# list1.net
KiCad netlist of a schematic drawn in Altium Designer
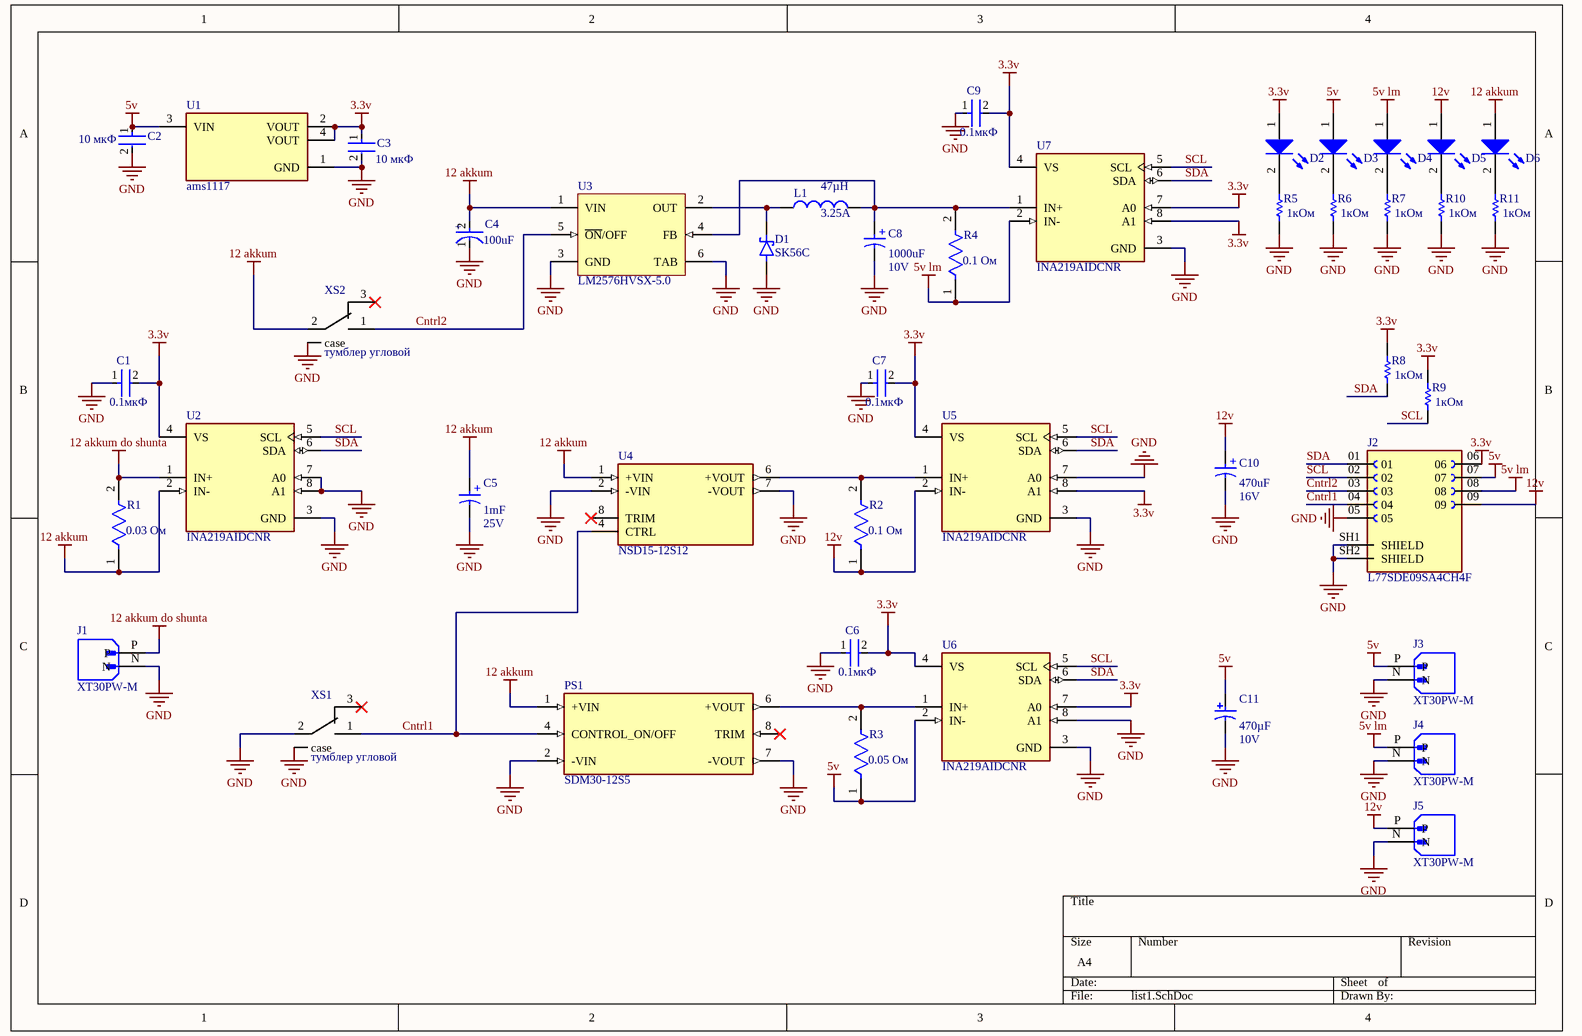
[diagram p0: list1.SchDoc]

(export (version "E")
  (design (tool "Eeschema 10.0.6"))
  (components
    (comp (ref "C1")
      (value "0.1мкФ")
      (footprint "FP-C0805C-DN-IPC_A")
      (description "CAP CER 0.1UF 50V X7R 0805")
      (fields
        (field (name "MANUFACTURER PART NUMBER") "C0805C104K5RACTU")
        (field (name "MANUFACTURER") "KEMET")
      )
      (libsource (lib "Components - cap0805") (part "CMP-2007-00279-2"))
    )
    (comp (ref "C2")
      (value "10 мкФ")
      (footprint "FP-C0805C-DN-IPC_A")
      (description "CAP CER 10UF 50V X7R 0805")
      (fields
        (field (name "MANUFACTURER PART NUMBER") "C0805C104K5RACTU")
        (field (name "MANUFACTURER") "KEMET")
      )
      (libsource (lib "Components - cap0805") (part "CMP-2007-00279-2"))
    )
    (comp (ref "C3")
      (value "10 мкФ")
      (footprint "FP-C0805C-DN-IPC_A")
      (description "CAP CER 10UF 50V X7R 0805")
      (fields
        (field (name "MANUFACTURER PART NUMBER") "C0805C104K5RACTU")
        (field (name "MANUFACTURER") "KEMET")
      )
      (libsource (lib "Components - cap0805") (part "CMP-2007-00279-2"))
    )
    (comp (ref "C4")
      (value "T495D107K016ATE125")
      (footprint "FP-T495D107K016ATE125-MFG")
      (description "CAP TANT 100UF 10% 16V 2917")
      (fields
        (field (name "CAPACITANCE") "100uF")
        (field (name "VOLTAGE") "16V")
        (field (name "TOLERANCE") "10%")
      )
      (libsource (lib "Altium Content Vault") (part "a00bbbee19879c290e62620ae7e47b1"))
    )
    (comp (ref "C5")
      (value "865060257010")
      (footprint "10*12.5")
      (description "865060257010 WCAP-ASLL Aluminum Electrolytic Capacitors 1000uf 25V")
      (fields
        (field (name "VOLTAGE RATING") "25V")
        (field (name "CAPACITANCE") "1mF")
        (field (name "TOLERANCE") "20%")
      )
      (libsource (lib "Components - 06.07.24 - 21") (part "konder"))
    )
    (comp (ref "C6")
      (value "0.1мкФ")
      (footprint "FP-C0805C-DN-IPC_A")
      (description "CAP CER 0.1UF 50V X7R 0805")
      (fields
        (field (name "MANUFACTURER PART NUMBER") "C0805C104K5RACTU")
        (field (name "MANUFACTURER") "KEMET")
      )
      (libsource (lib "Components - cap0805") (part "CMP-2007-00279-2"))
    )
    (comp (ref "C7")
      (value "0.1мкФ")
      (footprint "FP-C0805C-DN-IPC_A")
      (description "CAP CER 0.1UF 50V X7R 0805")
      (fields
        (field (name "MANUFACTURER PART NUMBER") "C0805C104K5RACTU")
        (field (name "MANUFACTURER") "KEMET")
      )
      (libsource (lib "Components - cap0805") (part "CMP-2007-00279-2"))
    )
    (comp (ref "C8")
      (value "865060257010")
      (footprint "WCAP-ASLL_D10H10.5")
      (description "865060257010 WCAP-ASLL Aluminum Electrolytic Capacitors 1000uf 10v")
      (fields
        (field (name "VOLTAGE RATING") "10V")
        (field (name "CAPACITANCE") "1000uF")
        (field (name "TOLERANCE") "20%")
      )
      (libsource (lib "Components - 06.07.24 - 21") (part "CMP-03913-54202466-2"))
    )
    (comp (ref "C9")
      (value "0.1мкФ")
      (footprint "FP-C0805C-DN-IPC_A")
      (description "CAP CER 0.1UF 50V X7R 0805")
      (fields
        (field (name "MANUFACTURER PART NUMBER") "C0805C104K5RACTU")
        (field (name "MANUFACTURER") "KEMET")
      )
      (libsource (lib "Components - cap0805") (part "CMP-2007-00279-2"))
    )
    (comp (ref "C10")
      (value "865060257010")
      (footprint "WCAP-ASLL_D10H10.5")
      (description "865060257010 WCAP-ASLL Aluminum Electrolytic Capacitors 470uf 16v")
      (fields
        (field (name "VOLTAGE RATING") "16V")
        (field (name "CAPACITANCE") "470uF")
        (field (name "TOLERANCE") "20%")
      )
      (libsource (lib "Components - 06.07.24 - 21") (part "CMP-03913-54202466-2"))
    )
    (comp (ref "C11")
      (value "EEEFK1C471P")
      (footprint "PNSC-FK-V-F_V")
      (fields
        (field (name "CAPACITANCE") "470µF")
        (field (name "MANUFACTURER") "Panasonic")
        (field (name "RATED VOLTAGE") "10V")
      )
      (libsource (lib "Altium Content Vault") (part "CAP-P-2"))
    )
    (comp (ref "D1")
      (value "SK56C")
      (footprint "DIOM6859X262N")
      (description "5A, 60V, Schottky Rectifier")
      (fields (field (name "MF") "Taiwan Semiconductor"))
      (libsource (lib "SK56C") (part "SK56C"))
    )
    (comp (ref "D2")
      (value "Infrared, 1.5V, 30°")
      (footprint "WL-TIRC_3mm")
      (description "WL-TIRC THT Infrared Round Waterclear, 3mm, 60mW/sr, Infrared, 1.5V, 30°")
      (fields
        (field (name "MANUFACTURER PART NUMBER") "15400385F3590")
        (field (name "MANUFACTURER") "Wurth Elektronik")
      )
      (libsource (lib "WL-TIRC") (part "15400385F3590"))
    )
    (comp (ref "D3")
      (value "Infrared, 1.5V, 30°")
      (footprint "WL-TIRC_3mm")
      (description "WL-TIRC THT Infrared Round Waterclear, 3mm, 60mW/sr, Infrared, 1.5V, 30°")
      (fields
        (field (name "MANUFACTURER PART NUMBER") "15400385F3590")
        (field (name "MANUFACTURER") "Wurth Elektronik")
      )
      (libsource (lib "WL-TIRC") (part "15400385F3590"))
    )
    (comp (ref "D4")
      (value "Infrared, 1.5V, 30°")
      (footprint "WL-TIRC_3mm")
      (description "WL-TIRC THT Infrared Round Waterclear, 3mm, 60mW/sr, Infrared, 1.5V, 30°")
      (fields
        (field (name "MANUFACTURER PART NUMBER") "15400385F3590")
        (field (name "MANUFACTURER") "Wurth Elektronik")
      )
      (libsource (lib "WL-TIRC") (part "15400385F3590"))
    )
    (comp (ref "D5")
      (value "Infrared, 1.5V, 30°")
      (footprint "WL-TIRC_3mm")
      (description "WL-TIRC THT Infrared Round Waterclear, 3mm, 60mW/sr, Infrared, 1.5V, 30°")
      (fields
        (field (name "MANUFACTURER PART NUMBER") "15400385F3590")
        (field (name "MANUFACTURER") "Wurth Elektronik")
      )
      (libsource (lib "WL-TIRC") (part "15400385F3590"))
    )
    (comp (ref "D6")
      (value "Infrared, 1.5V, 30°")
      (footprint "WL-TIRC_3mm")
      (description "WL-TIRC THT Infrared Round Waterclear, 3mm, 60mW/sr, Infrared, 1.5V, 30°")
      (fields
        (field (name "MANUFACTURER PART NUMBER") "15400385F3590")
        (field (name "MANUFACTURER") "Wurth Elektronik")
      )
      (libsource (lib "WL-TIRC") (part "15400385F3590"))
    )
    (comp (ref "J1")
      (value "XT30PW-M")
      (footprint "AMASS_XT30PW-M")
      (description "Socket; DC supply; XT30; male; PIN: 2; on PCBs; THT; Colour: yellow")
      (fields (field (name "MF") "AMASS"))
      (libsource (lib "XT30PW-M") (part "XT30PW-M"))
    )
    (comp (ref "J2")
      (value "L77SDE09SA4CH4F")
      (footprint "AMPHENOL_L77SDE09SA4CH4F")
      (fields (field (name "MF") "Amphenol ICC (Commercial Products)"))
      (libsource (lib "L77SDE09SA4CH4F") (part "L77SDE09SA4CH4F"))
    )
    (comp (ref "J3")
      (value "XT30PW-M")
      (footprint "AMASS_XT30PW-M")
      (description "Socket; DC supply; XT30; male; PIN: 2; on PCBs; THT; Colour: yellow")
      (fields (field (name "MF") "AMASS"))
      (libsource (lib "") (part "XT30PW-M_1"))
    )
    (comp (ref "J4")
      (value "XT30PW-M")
      (footprint "AMASS_XT30PW-M")
      (description "Socket; DC supply; XT30; male; PIN: 2; on PCBs; THT; Colour: yellow")
      (fields (field (name "MF") "AMASS"))
      (libsource (lib "") (part "XT30PW-M_1"))
    )
    (comp (ref "J5")
      (value "XT30PW-M")
      (footprint "AMASS_XT30PW-M")
      (description "Socket; DC supply; XT30; male; PIN: 2; on PCBs; THT; Colour: yellow")
      (fields (field (name "MF") "AMASS"))
      (libsource (lib "") (part "XT30PW-M_1"))
    )
    (comp (ref "L1")
      (value "CDRH127/LDNP-470MC")
      (footprint "SUMI-CDRH127_V")
      (description "Power Inductor, 10 uH, +/- 20%, -40 to 100 degC, 2-Pin SMD, RoHS, Tape and Reel")
      (fields
        (field (name "MANUFACTURER") "Sumida")
        (field (name "CURRENT RATING") "3.25A")
        (field (name "INDUCTANCE") "47µH")
        (field (name "TOLERANCE") "±20%")
      )
      (libsource (lib "Altium Content Vault") (part "IND-2"))
    )
    (comp (ref "PS1")
      (value "SDM30-12S5")
      (footprint "CONV_SDM30-12S5")
      (description "Isolated Module DC DC Converter 1 Output 5V 5A 9.2V - 18V Input")
      (fields (field (name "DIGI-KEY_PART_NUMBER") "1866-4448-ND") (field (name "MF") "MEAN WELL"))
      (libsource (lib "SDM30-12S5") (part "SDM30-12S5"))
    )
    (comp (ref "R1")
      (value "CRCW25121R00FKEG")
      (footprint "FP-CRCW2512-e3-IPC_A")
      (description "RES Thick Film, 1Ω, 1%, 1W, 100ppm/°C, 2512")
      (fields (field (name "RESISTANCE") "0.03 Ом") (field (name "TOLERANCE") "1%"))
      (libsource (lib "Components - 2512 res") (part "CMP-02407-006956-1"))
    )
    (comp (ref "R2")
      (value "CRCW25121R00FKEG")
      (footprint "FP-CRCW2512-e3-IPC_A")
      (description "RES Thick Film, 1Ω, 1%, 1W, 100ppm/°C, 2512")
      (fields (field (name "RESISTANCE") "0.1 Ом") (field (name "TOLERANCE") "1%"))
      (libsource (lib "Components - 2512 res") (part "CMP-02407-006956-1"))
    )
    (comp (ref "R3")
      (value "CRCW25121R00FKEG")
      (footprint "FP-CRCW2512-e3-IPC_A")
      (description "RES Thick Film, 1Ω, 1%, 1W, 100ppm/°C, 2512")
      (fields (field (name "RESISTANCE") "0.05 Ом") (field (name "TOLERANCE") "1%"))
      (libsource (lib "Components - 2512 res") (part "CMP-02407-006956-1"))
    )
    (comp (ref "R4")
      (value "CRCW25121R00FKEG")
      (footprint "FP-CRCW2512-e3-IPC_A")
      (description "RES Thick Film, 1Ω, 1%, 1W, 100ppm/°C, 2512")
      (fields (field (name "RESISTANCE") "0.1 Ом") (field (name "TOLERANCE") "1%"))
      (libsource (lib "Components - 2512 res") (part "CMP-02407-006956-1"))
    )
    (comp (ref "R5")
      (value "ERJ-6ENF1001V")
      (footprint "RESC2013X70X40ML20T20")
      (description "Chip Resistor, 1 KOhm, +/- 1%, 0.125 W, -55 to 155 degC, 0805 (2012 Metric), RoHS, Tape and Reel")
      (fields (field (name "MANUFACTURER") "Panasonic") (field (name "PACKAGE QUANTITY") "1кОм"))
      (libsource (lib "Components res 0805") (part "CMP-2001-04375-5"))
    )
    (comp (ref "R6")
      (value "ERJ-6ENF1001V")
      (footprint "RESC2013X70X40ML20T20")
      (description "Chip Resistor, 1 KOhm, +/- 1%, 0.125 W, -55 to 155 degC, 0805 (2012 Metric), RoHS, Tape and Reel")
      (fields (field (name "MANUFACTURER") "Panasonic") (field (name "PACKAGE QUANTITY") "1кОм"))
      (libsource (lib "Components res 0805") (part "CMP-2001-04375-5"))
    )
    (comp (ref "R7")
      (value "ERJ-6ENF1001V")
      (footprint "RESC2013X70X40ML20T20")
      (description "Chip Resistor, 1 KOhm, +/- 1%, 0.125 W, -55 to 155 degC, 0805 (2012 Metric), RoHS, Tape and Reel")
      (fields (field (name "MANUFACTURER") "Panasonic") (field (name "PACKAGE QUANTITY") "1кОм"))
      (libsource (lib "Components res 0805") (part "CMP-2001-04375-5"))
    )
    (comp (ref "R8")
      (value "ERJ-6ENF1001V")
      (footprint "RESC2013X70X40ML20T20")
      (description "Chip Resistor, 1 KOhm, +/- 1%, 0.125 W, -55 to 155 degC, 0805 (2012 Metric), RoHS, Tape and Reel")
      (fields (field (name "MANUFACTURER") "Panasonic") (field (name "PACKAGE QUANTITY") "1кОм"))
      (libsource (lib "Components res 0805") (part "CMP-2001-04375-5"))
    )
    (comp (ref "R9")
      (value "ERJ-6ENF1001V")
      (footprint "RESC2013X70X40ML20T20")
      (description "Chip Resistor, 1 KOhm, +/- 1%, 0.125 W, -55 to 155 degC, 0805 (2012 Metric), RoHS, Tape and Reel")
      (fields (field (name "MANUFACTURER") "Panasonic") (field (name "PACKAGE QUANTITY") "1кОм"))
      (libsource (lib "Components res 0805") (part "CMP-2001-04375-5"))
    )
    (comp (ref "R10")
      (value "ERJ-6ENF1001V")
      (footprint "RESC2013X70X40ML20T20")
      (description "Chip Resistor, 1 KOhm, +/- 1%, 0.125 W, -55 to 155 degC, 0805 (2012 Metric), RoHS, Tape and Reel")
      (fields (field (name "MANUFACTURER") "Panasonic") (field (name "PACKAGE QUANTITY") "1кОм"))
      (libsource (lib "Components res 0805") (part "CMP-2001-04375-5"))
    )
    (comp (ref "R11")
      (value "ERJ-6ENF1001V")
      (footprint "RESC2013X70X40ML20T20")
      (description "Chip Resistor, 1 KOhm, +/- 1%, 0.125 W, -55 to 155 degC, 0805 (2012 Metric), RoHS, Tape and Reel")
      (fields (field (name "MANUFACTURER") "Panasonic") (field (name "PACKAGE QUANTITY") "1кОм"))
      (libsource (lib "Components res 0805") (part "CMP-2001-04375-5"))
    )
    (comp (ref "U1")
      (value "ams1117")
      (footprint "FP-ams1117-IPC_A")
      (description "1A LOW DROPOUT VOLTAGE REGULATOR 3.3V")
      (libsource (lib "Components - ldo 3.3 ams1117") (part "CMP-209535-000002-1"))
    )
    (comp (ref "U2")
      (value "INA219AIDCNR")
      (footprint "FP-DCN0008A-IPC_C")
      (description "IC CURRENT MONITOR 1% SOT23-8")
      (libsource (lib "Components - ina219") (part "CMP-0704-00041-3"))
    )
    (comp (ref "U3")
      (value "LM2576HVSX-5.0")
      (footprint "KTT0005B_M")
      (description "SIMPLE SWITCHER® 3A Step-Down Voltage Regulator, 5-pin TO-263")
      (fields (field (name "MANUFACTURER") "Texas Instruments"))
      (libsource (lib "Altium Content Vault") (part "PM-REG-LM2575HVS-12"))
    )
    (comp (ref "U4")
      (value "NSD15-12S12")
      (footprint "CONV_NSD15-12S5")
      (description "Isolated Module DC DC Converter 1 Output 5V 3A 9.4V - 36V Input")
      (fields (field (name "MP") "NSD15-12S5") (field (name "MF") "MEAN WELL"))
      (libsource (lib "SnapEDAsch") (part "NSD15-12S12"))
    )
    (comp (ref "U5")
      (value "INA219AIDCNR")
      (footprint "FP-DCN0008A-IPC_C")
      (description "IC CURRENT MONITOR 1% SOT23-8")
      (libsource (lib "Components - ina219") (part "CMP-0704-00041-3"))
    )
    (comp (ref "U6")
      (value "INA219AIDCNR")
      (footprint "FP-DCN0008A-IPC_C")
      (description "IC CURRENT MONITOR 1% SOT23-8")
      (libsource (lib "Components - ina219") (part "CMP-0704-00041-3"))
    )
    (comp (ref "U7")
      (value "INA219AIDCNR")
      (footprint "FP-DCN0008A-IPC_C")
      (description "IC CURRENT MONITOR 1% SOT23-8")
      (libsource (lib "Components - ina219") (part "CMP-0704-00041-3"))
    )
    (comp (ref "XS1")
      (value "тумблер угловой")
      (footprint "тумблер угловой")
      (description "SMTS-102-2C4")
      (libsource (lib "bibla2") (part "тумблер угловой"))
    )
    (comp (ref "XS2")
      (value "тумблер угловой")
      (footprint "тумблер угловой")
      (description "SMTS-102-2C4")
      (libsource (lib "bibla2") (part "тумблер угловой"))
    )
  )
  (nets
    (net (code "1") (name "/Cntrl1") (class "Default")
      (node (ref "J2") (pin "04") (pinfunction "04_04") (pintype "passive"))
      (node (ref "PS1") (pin "4") (pinfunction "CONTROL_ON/OFF_4") (pintype "input"))
      (node (ref "U4") (pin "4") (pinfunction "CTRL_4") (pintype "passive"))
      (node (ref "XS1") (pin "1") (pinfunction "1_1") (pintype "passive"))
    )
    (net (code "2") (name "/Cntrl2") (class "Default")
      (node (ref "J2") (pin "03") (pinfunction "03_03") (pintype "passive"))
      (node (ref "U3") (pin "5") (pinfunction "~{ON}/OFF_5") (pintype "input"))
      (node (ref "XS2") (pin "1") (pinfunction "1_1") (pintype "passive"))
    )
    (net (code "3") (name "/SCL") (class "Default")
      (node (ref "J2") (pin "02") (pinfunction "02_02") (pintype "passive"))
      (node (ref "R9") (pin "1") (pinfunction "1_1") (pintype "passive"))
      (node (ref "U2") (pin "5") (pinfunction "SCL_5") (pintype "input"))
      (node (ref "U5") (pin "5") (pinfunction "SCL_5") (pintype "input"))
      (node (ref "U6") (pin "5") (pinfunction "SCL_5") (pintype "input"))
      (node (ref "U7") (pin "5") (pinfunction "SCL_5") (pintype "input"))
    )
    (net (code "4") (name "/SDA") (class "Default")
      (node (ref "J2") (pin "01") (pinfunction "01_01") (pintype "passive"))
      (node (ref "R8") (pin "1") (pinfunction "1_1") (pintype "passive"))
      (node (ref "U2") (pin "6") (pinfunction "SDA_6") (pintype "bidirectional"))
      (node (ref "U5") (pin "6") (pinfunction "SDA_6") (pintype "bidirectional"))
      (node (ref "U6") (pin "6") (pinfunction "SDA_6") (pintype "bidirectional"))
      (node (ref "U7") (pin "6") (pinfunction "SDA_6") (pintype "bidirectional"))
    )
    (net (code "5") (name "3.3v") (class "Default")
      (node (ref "C1") (pin "2") (pinfunction "2_2") (pintype "passive"))
      (node (ref "C3") (pin "1") (pinfunction "1_1") (pintype "passive"))
      (node (ref "C6") (pin "2") (pinfunction "2_2") (pintype "passive"))
      (node (ref "C7") (pin "2") (pinfunction "2_2") (pintype "passive"))
      (node (ref "C9") (pin "2") (pinfunction "2_2") (pintype "passive"))
      (node (ref "D2") (pin "1") (pinfunction "A_1") (pintype "passive"))
      (node (ref "J2") (pin "06") (pinfunction "06_06") (pintype "passive"))
      (node (ref "R8") (pin "2") (pinfunction "2_2") (pintype "passive"))
      (node (ref "R9") (pin "2") (pinfunction "2_2") (pintype "passive"))
      (node (ref "U1") (pin "2") (pinfunction "VOUT_2") (pintype "passive"))
      (node (ref "U1") (pin "4") (pinfunction "VOUT_4") (pintype "passive"))
      (node (ref "U2") (pin "4") (pinfunction "VS_4") (pintype "power_in"))
      (node (ref "U5") (pin "4") (pinfunction "VS_4") (pintype "power_in"))
      (node (ref "U5") (pin "8") (pinfunction "A1_8") (pintype "input"))
      (node (ref "U6") (pin "4") (pinfunction "VS_4") (pintype "power_in"))
      (node (ref "U6") (pin "7") (pinfunction "A0_7") (pintype "input"))
      (node (ref "U7") (pin "4") (pinfunction "VS_4") (pintype "power_in"))
      (node (ref "U7") (pin "7") (pinfunction "A0_7") (pintype "input"))
      (node (ref "U7") (pin "8") (pinfunction "A1_8") (pintype "input"))
    )
    (net (code "6") (name "5v") (class "Default")
      (node (ref "C11") (pin "1") (pinfunction "1_1") (pintype "passive"))
      (node (ref "C2") (pin "1") (pinfunction "1_1") (pintype "passive"))
      (node (ref "D3") (pin "1") (pinfunction "A_1") (pintype "passive"))
      (node (ref "J2") (pin "07") (pinfunction "07_07") (pintype "passive"))
      (node (ref "J3") (pin "P") (pinfunction "P_P") (pintype "power_in"))
      (node (ref "R3") (pin "1") (pinfunction "1_1") (pintype "passive"))
      (node (ref "U1") (pin "3") (pinfunction "VIN_3") (pintype "power_in"))
      (node (ref "U6") (pin "2") (pinfunction "IN-_2") (pintype "input"))
    )
    (net (code "7") (name "5v lm") (class "Default")
      (node (ref "D4") (pin "1") (pinfunction "A_1") (pintype "passive"))
      (node (ref "J2") (pin "08") (pinfunction "08_08") (pintype "passive"))
      (node (ref "J4") (pin "P") (pinfunction "P_P") (pintype "power_in"))
      (node (ref "R4") (pin "1") (pinfunction "1_1") (pintype "passive"))
      (node (ref "U7") (pin "2") (pinfunction "IN-_2") (pintype "input"))
    )
    (net (code "8") (name "12 akkum") (class "Default")
      (node (ref "C4") (pin "2") (pinfunction "A_2") (pintype "passive"))
      (node (ref "C5") (pin "1") (pinfunction "P_1") (pintype "passive"))
      (node (ref "D6") (pin "1") (pinfunction "A_1") (pintype "passive"))
      (node (ref "PS1") (pin "1") (pinfunction "+VIN_1") (pintype "input"))
      (node (ref "R1") (pin "1") (pinfunction "1_1") (pintype "passive"))
      (node (ref "U2") (pin "2") (pinfunction "IN-_2") (pintype "input"))
      (node (ref "U3") (pin "1") (pinfunction "VIN_1") (pintype "power_in"))
      (node (ref "U4") (pin "1") (pinfunction "+VIN_1") (pintype "input"))
      (node (ref "XS2") (pin "2") (pinfunction "2_2") (pintype "passive"))
    )
    (net (code "9") (name "12 akkum do shunta") (class "Default")
      (node (ref "J1") (pin "P") (pinfunction "P_P") (pintype "power_in"))
      (node (ref "R1") (pin "2") (pinfunction "2_2") (pintype "passive"))
      (node (ref "U2") (pin "1") (pinfunction "IN+_1") (pintype "passive"))
    )
    (net (code "10") (name "12v") (class "Default")
      (node (ref "C10") (pin "1") (pinfunction "P_1") (pintype "passive"))
      (node (ref "D5") (pin "1") (pinfunction "A_1") (pintype "passive"))
      (node (ref "J2") (pin "09") (pinfunction "09_09") (pintype "passive"))
      (node (ref "J5") (pin "P") (pinfunction "P_P") (pintype "power_in"))
      (node (ref "R2") (pin "1") (pinfunction "1_1") (pintype "passive"))
      (node (ref "U5") (pin "2") (pinfunction "IN-_2") (pintype "input"))
    )
    (net (code "11") (name "GND") (class "Default")
      (node (ref "C1") (pin "1") (pinfunction "1_1") (pintype "passive"))
      (node (ref "C10") (pin "2") (pinfunction "N_2") (pintype "passive"))
      (node (ref "C11") (pin "2") (pinfunction "2_2") (pintype "passive"))
      (node (ref "C2") (pin "2") (pinfunction "2_2") (pintype "passive"))
      (node (ref "C3") (pin "2") (pinfunction "2_2") (pintype "passive"))
      (node (ref "C4") (pin "1") (pinfunction "C_1") (pintype "passive"))
      (node (ref "C5") (pin "2") (pinfunction "N_2") (pintype "passive"))
      (node (ref "C6") (pin "1") (pinfunction "1_1") (pintype "passive"))
      (node (ref "C7") (pin "1") (pinfunction "1_1") (pintype "passive"))
      (node (ref "C8") (pin "2") (pinfunction "N_2") (pintype "passive"))
      (node (ref "C9") (pin "1") (pinfunction "1_1") (pintype "passive"))
      (node (ref "D1") (pin "A") (pinfunction "A_A") (pintype "passive"))
      (node (ref "J1") (pin "N") (pinfunction "N_N") (pintype "power_in"))
      (node (ref "J2") (pin "05") (pinfunction "05_05") (pintype "passive"))
      (node (ref "J2") (pin "SH1") (pinfunction "SHIELD_SH1") (pintype "passive"))
      (node (ref "J2") (pin "SH2") (pinfunction "SHIELD_SH2") (pintype "passive"))
      (node (ref "J3") (pin "N") (pinfunction "N_N") (pintype "power_in"))
      (node (ref "J4") (pin "N") (pinfunction "N_N") (pintype "power_in"))
      (node (ref "J5") (pin "N") (pinfunction "N_N") (pintype "power_in"))
      (node (ref "PS1") (pin "2") (pinfunction "-VIN_2") (pintype "input"))
      (node (ref "PS1") (pin "7") (pinfunction "-VOUT_7") (pintype "output"))
      (node (ref "R10") (pin "1") (pinfunction "1_1") (pintype "passive"))
      (node (ref "R11") (pin "1") (pinfunction "1_1") (pintype "passive"))
      (node (ref "R5") (pin "1") (pinfunction "1_1") (pintype "passive"))
      (node (ref "R6") (pin "1") (pinfunction "1_1") (pintype "passive"))
      (node (ref "R7") (pin "1") (pinfunction "1_1") (pintype "passive"))
      (node (ref "U1") (pin "1") (pinfunction "GND_1") (pintype "passive"))
      (node (ref "U2") (pin "3") (pinfunction "GND_3") (pintype "power_in"))
      (node (ref "U2") (pin "7") (pinfunction "A0_7") (pintype "input"))
      (node (ref "U2") (pin "8") (pinfunction "A1_8") (pintype "input"))
      (node (ref "U3") (pin "3") (pinfunction "GND_3") (pintype "power_in"))
      (node (ref "U3") (pin "6") (pinfunction "TAB_6") (pintype "power_in"))
      (node (ref "U4") (pin "2") (pinfunction "-VIN_2") (pintype "input"))
      (node (ref "U4") (pin "7") (pinfunction "-VOUT_7") (pintype "output"))
      (node (ref "U5") (pin "3") (pinfunction "GND_3") (pintype "power_in"))
      (node (ref "U5") (pin "7") (pinfunction "A0_7") (pintype "input"))
      (node (ref "U6") (pin "3") (pinfunction "GND_3") (pintype "power_in"))
      (node (ref "U6") (pin "8") (pinfunction "A1_8") (pintype "input"))
      (node (ref "U7") (pin "3") (pinfunction "GND_3") (pintype "power_in"))
      (node (ref "XS1") (pin "0") (pinfunction "case_0") (pintype "passive"))
      (node (ref "XS1") (pin "2") (pinfunction "2_2") (pintype "passive"))
      (node (ref "XS2") (pin "0") (pinfunction "case_0") (pintype "passive"))
    )
    (net (code "12") (name "Net-(C8-P)") (class "Default")
      (node (ref "C8") (pin "1") (pinfunction "P_1") (pintype "passive"))
      (node (ref "L1") (pin "2") (pinfunction "2_2") (pintype "passive"))
      (node (ref "R4") (pin "2") (pinfunction "2_2") (pintype "passive"))
      (node (ref "U3") (pin "4") (pinfunction "FB_4") (pintype "input"))
      (node (ref "U7") (pin "1") (pinfunction "IN+_1") (pintype "passive"))
    )
    (net (code "13") (name "Net-(D1-K)") (class "Default")
      (node (ref "D1") (pin "C") (pinfunction "K_C") (pintype "passive"))
      (node (ref "L1") (pin "1") (pinfunction "1_1") (pintype "passive"))
      (node (ref "U3") (pin "2") (pinfunction "OUT_2") (pintype "power_in"))
    )
    (net (code "14") (name "Net-(D2-K)") (class "Default")
      (node (ref "D2") (pin "2") (pinfunction "K_2") (pintype "passive"))
      (node (ref "R5") (pin "2") (pinfunction "2_2") (pintype "passive"))
    )
    (net (code "15") (name "Net-(D3-K)") (class "Default")
      (node (ref "D3") (pin "2") (pinfunction "K_2") (pintype "passive"))
      (node (ref "R6") (pin "2") (pinfunction "2_2") (pintype "passive"))
    )
    (net (code "16") (name "Net-(D4-K)") (class "Default")
      (node (ref "D4") (pin "2") (pinfunction "K_2") (pintype "passive"))
      (node (ref "R7") (pin "2") (pinfunction "2_2") (pintype "passive"))
    )
    (net (code "17") (name "Net-(D5-K)") (class "Default")
      (node (ref "D5") (pin "2") (pinfunction "K_2") (pintype "passive"))
      (node (ref "R10") (pin "2") (pinfunction "2_2") (pintype "passive"))
    )
    (net (code "18") (name "Net-(D6-K)") (class "Default")
      (node (ref "D6") (pin "2") (pinfunction "K_2") (pintype "passive"))
      (node (ref "R11") (pin "2") (pinfunction "2_2") (pintype "passive"))
    )
    (net (code "19") (name "Net-(PS1-+VOUT)") (class "Default")
      (node (ref "PS1") (pin "6") (pinfunction "+VOUT_6") (pintype "output"))
      (node (ref "R3") (pin "2") (pinfunction "2_2") (pintype "passive"))
      (node (ref "U6") (pin "1") (pinfunction "IN+_1") (pintype "passive"))
    )
    (net (code "20") (name "Net-(U4-+VOUT)") (class "Default")
      (node (ref "R2") (pin "2") (pinfunction "2_2") (pintype "passive"))
      (node (ref "U4") (pin "6") (pinfunction "+VOUT_6") (pintype "output"))
      (node (ref "U5") (pin "1") (pinfunction "IN+_1") (pintype "passive"))
    )
    (net (code "21") (name "unconnected-(PS1-TRIM-Pad8)") (class "Default")
      (node (ref "PS1") (pin "8") (pinfunction "TRIM_8") (pintype "input+no_connect"))
    )
    (net (code "22") (name "unconnected-(U4-TRIM-Pad8)") (class "Default")
      (node (ref "U4") (pin "8") (pinfunction "TRIM_8") (pintype "passive+no_connect"))
    )
    (net (code "23") (name "unconnected-(XS1-Pad3)") (class "Default")
      (node (ref "XS1") (pin "3") (pinfunction "3_3") (pintype "passive+no_connect"))
    )
    (net (code "24") (name "unconnected-(XS2-Pad3)") (class "Default")
      (node (ref "XS2") (pin "3") (pinfunction "3_3") (pintype "passive+no_connect"))
    )
  )
)
